# WaterMonitorV6_0.net
KiCad netlist of a schematic drawn in EAGLE
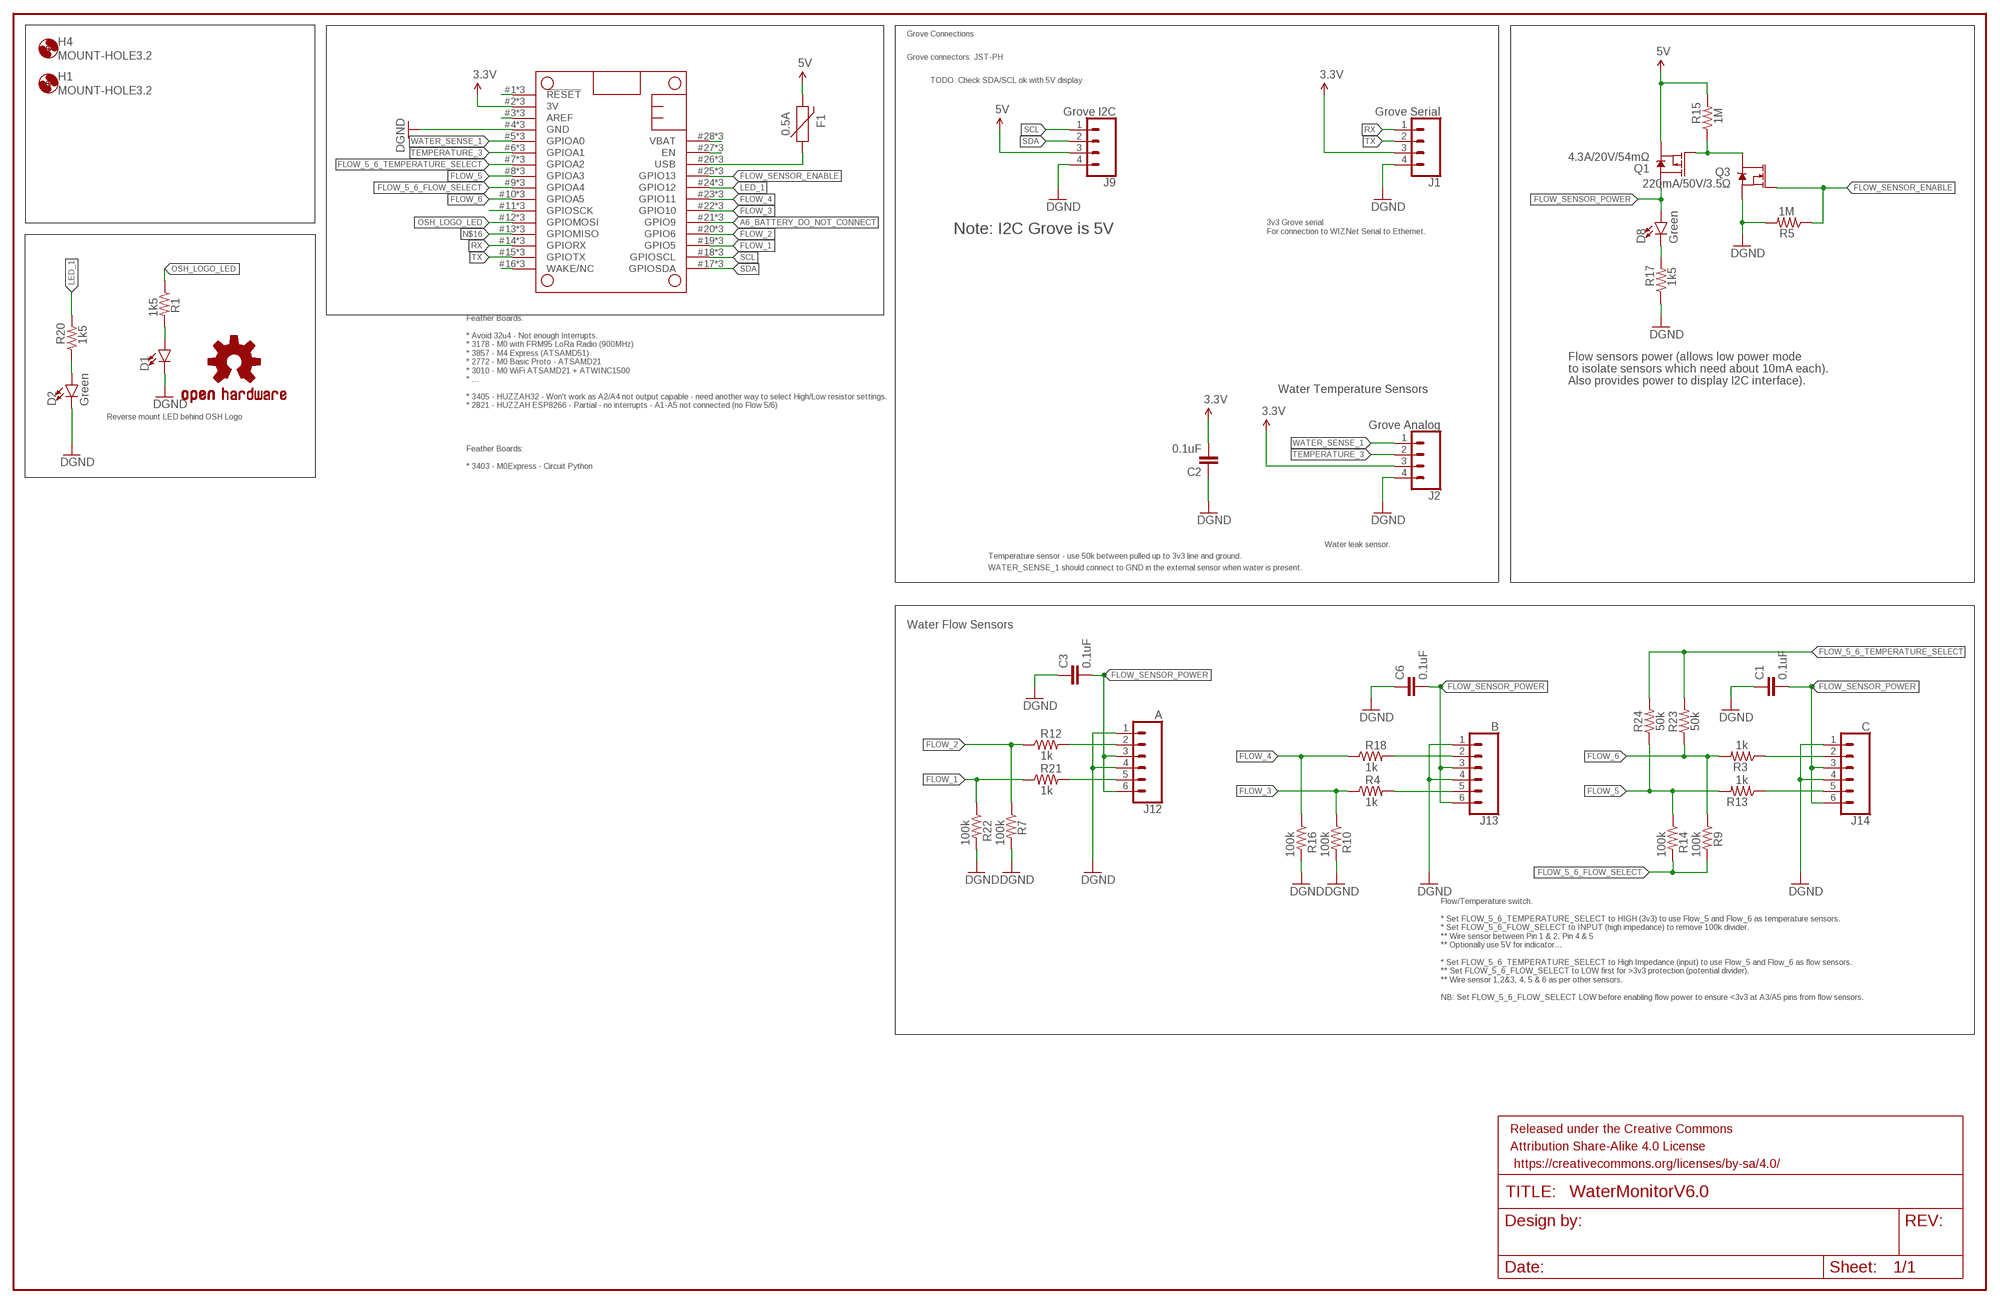
[diagram p0: schematic, sheet 1]

(export (version "E")
  (design (tool "Eeschema 10.0.6"))
  (components
    (comp (ref "C1")
      (value "0.1uF")
      (footprint "eagle-import:0805")
      (libsource (lib "eagle-import") (part "CAP0805"))
    )
    (comp (ref "C2")
      (value "0.1uF")
      (footprint "eagle-import:0805")
      (libsource (lib "eagle-import") (part "CAP0805"))
    )
    (comp (ref "C3")
      (value "0.1uF")
      (footprint "eagle-import:0805")
      (libsource (lib "eagle-import") (part "CAP0805"))
    )
    (comp (ref "C6")
      (value "0.1uF")
      (footprint "eagle-import:0805")
      (libsource (lib "eagle-import") (part "CAP0805"))
    )
    (comp (ref "D1")
      (value "LED1206-BOTTOM")
      (footprint "eagle-import:LED-1206-BOTTOM")
      (libsource (lib "eagle-import") (part "LED1206-BOTTOM"))
    )
    (comp (ref "D2")
      (value "Green")
      (footprint "eagle-import:LED-1206")
      (libsource (lib "eagle-import") (part "LED-BLUE1206"))
    )
    (comp (ref "D8")
      (value "Green")
      (footprint "eagle-import:LED-1206")
      (libsource (lib "eagle-import") (part "LED-BLUE1206"))
    )
    (comp (ref "F1")
      (value "0.5A")
      (footprint "eagle-import:1206")
      (libsource (lib "eagle-import") (part "PPTC_HALF-AMP"))
    )
    (comp (ref "FRAME2")
      (value "FRAME-LEDGER")
      (footprint "eagle-import:CREATIVE_COMMONS")
      (libsource (lib "eagle-import") (part "FRAME-LEDGER"))
    )
    (comp (ref "H1")
      (value "MOUNT-HOLE3.2")
      (footprint "eagle-import:3,2")
      (libsource (lib "eagle-import") (part "MOUNT-HOLE3.2"))
    )
    (comp (ref "H4")
      (value "MOUNT-HOLE3.2")
      (footprint "eagle-import:3,2")
      (libsource (lib "eagle-import") (part "MOUNT-HOLE3.2"))
    )
    (comp (ref "J1")
      (value "Grove Serial")
      (footprint "eagle-import:JST-4-PTH-VERT")
      (libsource (lib "eagle-import") (part "CONN_04JST-PTH-VERT"))
    )
    (comp (ref "J2")
      (value "Grove Analog")
      (footprint "eagle-import:JST-4-PTH-VERT")
      (libsource (lib "eagle-import") (part "CONN_04JST-PTH-VERT"))
    )
    (comp (ref "J9")
      (value "Grove I2C")
      (footprint "eagle-import:JST-4-PTH-VERT")
      (libsource (lib "eagle-import") (part "CONN_04JST-PTH-VERT"))
    )
    (comp (ref "J12")
      (value "A")
      (footprint "eagle-import:RJ11-6")
      (libsource (lib "eagle-import") (part "RJ11-6"))
    )
    (comp (ref "J13")
      (value "B")
      (footprint "eagle-import:RJ11-6")
      (libsource (lib "eagle-import") (part "RJ11-6"))
    )
    (comp (ref "J14")
      (value "C")
      (footprint "eagle-import:RJ11-6")
      (libsource (lib "eagle-import") (part "RJ11-6"))
    )
    (comp (ref "LOGO1")
      (value "OSHW-LOGOM")
      (footprint "eagle-import:OSHW-LOGO-M")
      (libsource (lib "eagle-import") (part "OSHW-LOGOM"))
    )
    (comp (ref "MS1")
      (value "FEATHERWINGFEATHEWING_BREAKOUT")
      (footprint "eagle-import:FEATHERWING_BREAKOUT")
      (libsource (lib "eagle-import") (part "FEATHERWINGFEATHEWING_BREAKOUT"))
    )
    (comp (ref "Q1")
      (value "4.3A/20V/54mΩ")
      (footprint "eagle-import:SOT23-3")
      (libsource (lib "eagle-import") (part "MOSFET_PCH-IRLML2244"))
    )
    (comp (ref "Q3")
      (value "220mA/50V/3.5Ω")
      (footprint "eagle-import:SOT23-3")
      (libsource (lib "eagle-import") (part "MOSFET-NCH-BSS138"))
    )
    (comp (ref "R1")
      (value "1k5")
      (footprint "eagle-import:0805")
      (libsource (lib "eagle-import") (part "RESISTOR0805"))
    )
    (comp (ref "R3")
      (value "1k")
      (footprint "eagle-import:0805")
      (libsource (lib "eagle-import") (part "RESISTOR0805"))
    )
    (comp (ref "R4")
      (value "1k")
      (footprint "eagle-import:0805")
      (libsource (lib "eagle-import") (part "RESISTOR0805"))
    )
    (comp (ref "R5")
      (value "1M")
      (footprint "eagle-import:0805")
      (libsource (lib "eagle-import") (part "RESISTOR0805"))
    )
    (comp (ref "R7")
      (value "100k")
      (footprint "eagle-import:0805")
      (libsource (lib "eagle-import") (part "RESISTOR0805"))
    )
    (comp (ref "R9")
      (value "100k")
      (footprint "eagle-import:0805")
      (libsource (lib "eagle-import") (part "RESISTOR0805"))
    )
    (comp (ref "R10")
      (value "100k")
      (footprint "eagle-import:0805")
      (libsource (lib "eagle-import") (part "RESISTOR0805"))
    )
    (comp (ref "R12")
      (value "1k")
      (footprint "eagle-import:0805")
      (libsource (lib "eagle-import") (part "RESISTOR0805"))
    )
    (comp (ref "R13")
      (value "1k")
      (footprint "eagle-import:0805")
      (libsource (lib "eagle-import") (part "RESISTOR0805"))
    )
    (comp (ref "R14")
      (value "100k")
      (footprint "eagle-import:0805")
      (libsource (lib "eagle-import") (part "RESISTOR0805"))
    )
    (comp (ref "R15")
      (value "1M")
      (footprint "eagle-import:0805")
      (libsource (lib "eagle-import") (part "RESISTOR0805"))
    )
    (comp (ref "R16")
      (value "100k")
      (footprint "eagle-import:0805")
      (libsource (lib "eagle-import") (part "RESISTOR0805"))
    )
    (comp (ref "R17")
      (value "1k5")
      (footprint "eagle-import:0805")
      (libsource (lib "eagle-import") (part "RESISTOR0805"))
    )
    (comp (ref "R18")
      (value "1k")
      (footprint "eagle-import:0805")
      (libsource (lib "eagle-import") (part "RESISTOR0805"))
    )
    (comp (ref "R20")
      (value "1k5")
      (footprint "eagle-import:0805")
      (libsource (lib "eagle-import") (part "RESISTOR0805"))
    )
    (comp (ref "R21")
      (value "1k")
      (footprint "eagle-import:0805")
      (libsource (lib "eagle-import") (part "RESISTOR0805"))
    )
    (comp (ref "R22")
      (value "100k")
      (footprint "eagle-import:0805")
      (libsource (lib "eagle-import") (part "RESISTOR0805"))
    )
    (comp (ref "R23")
      (value "50k")
      (footprint "eagle-import:0805")
      (libsource (lib "eagle-import") (part "RESISTOR0805"))
    )
    (comp (ref "R24")
      (value "50k")
      (footprint "eagle-import:0805")
      (libsource (lib "eagle-import") (part "RESISTOR0805"))
    )
  )
  (nets
    (net (code "1") (name "3.3V") (class "Default")
      (node (ref "C2") (pin "2") (pinfunction "2_2") (pintype "passive"))
      (node (ref "J1") (pin "3") (pinfunction "3_3") (pintype "passive"))
      (node (ref "J2") (pin "3") (pinfunction "3_3") (pintype "passive"))
      (node (ref "MS1") (pin "#2") (pinfunction "3V_#2") (pintype "power_in"))
      (node (ref "MS1") (pin "2") (pinfunction "3V_2") (pintype "power_in"))
      (node (ref "MS1") (pin "@2") (pinfunction "3V_@2") (pintype "power_in"))
    )
    (net (code "2") (name "5V") (class "Default")
      (node (ref "F1") (pin "2") (pinfunction "2_2") (pintype "bidirectional"))
      (node (ref "J9") (pin "3") (pinfunction "3_3") (pintype "passive"))
      (node (ref "Q1") (pin "2") (pinfunction "S_2") (pintype "bidirectional"))
      (node (ref "R15") (pin "2") (pinfunction "2_2") (pintype "passive"))
    )
    (net (code "3") (name "A6_BATTERY_DO_NOT_CONNECT") (class "Default")
      (node (ref "MS1") (pin "#21") (pinfunction "GPIO9_#21") (pintype "bidirectional"))
      (node (ref "MS1") (pin "21") (pinfunction "GPIO9_21") (pintype "bidirectional"))
      (node (ref "MS1") (pin "@21") (pinfunction "GPIO9_@21") (pintype "bidirectional"))
    )
    (net (code "4") (name "DGND") (class "Default")
      (node (ref "C1") (pin "1") (pinfunction "1_1") (pintype "passive"))
      (node (ref "C2") (pin "1") (pinfunction "1_1") (pintype "passive"))
      (node (ref "C3") (pin "1") (pinfunction "1_1") (pintype "passive"))
      (node (ref "C6") (pin "1") (pinfunction "1_1") (pintype "passive"))
      (node (ref "D1") (pin "C") (pinfunction "C_C") (pintype "passive"))
      (node (ref "D2") (pin "C") (pinfunction "C_C") (pintype "passive"))
      (node (ref "J1") (pin "4") (pinfunction "4_4") (pintype "passive"))
      (node (ref "J12") (pin "1") (pinfunction "1_1") (pintype "passive"))
      (node (ref "J12") (pin "4") (pinfunction "4_4") (pintype "passive"))
      (node (ref "J13") (pin "1") (pinfunction "1_1") (pintype "passive"))
      (node (ref "J13") (pin "4") (pinfunction "4_4") (pintype "passive"))
      (node (ref "J14") (pin "1") (pinfunction "1_1") (pintype "passive"))
      (node (ref "J14") (pin "4") (pinfunction "4_4") (pintype "passive"))
      (node (ref "J2") (pin "4") (pinfunction "4_4") (pintype "passive"))
      (node (ref "J9") (pin "4") (pinfunction "4_4") (pintype "passive"))
      (node (ref "MS1") (pin "#4") (pinfunction "GND_#4") (pintype "power_in"))
      (node (ref "MS1") (pin "4") (pinfunction "GND_4") (pintype "power_in"))
      (node (ref "MS1") (pin "@4") (pinfunction "GND_@4") (pintype "power_in"))
      (node (ref "Q3") (pin "2") (pinfunction "S_2") (pintype "bidirectional"))
      (node (ref "R10") (pin "2") (pinfunction "2_2") (pintype "passive"))
      (node (ref "R16") (pin "2") (pinfunction "2_2") (pintype "passive"))
      (node (ref "R17") (pin "1") (pinfunction "1_1") (pintype "passive"))
      (node (ref "R22") (pin "2") (pinfunction "2_2") (pintype "passive"))
      (node (ref "R5") (pin "2") (pinfunction "2_2") (pintype "passive"))
      (node (ref "R7") (pin "2") (pinfunction "2_2") (pintype "passive"))
    )
    (net (code "5") (name "FLOW_1") (class "Default")
      (node (ref "MS1") (pin "#19") (pinfunction "GPIO5_#19") (pintype "bidirectional"))
      (node (ref "MS1") (pin "19") (pinfunction "GPIO5_19") (pintype "bidirectional"))
      (node (ref "MS1") (pin "@19") (pinfunction "GPIO5_@19") (pintype "bidirectional"))
      (node (ref "R21") (pin "1") (pinfunction "1_1") (pintype "passive"))
      (node (ref "R22") (pin "1") (pinfunction "1_1") (pintype "passive"))
    )
    (net (code "6") (name "FLOW_2") (class "Default")
      (node (ref "MS1") (pin "#20") (pinfunction "GPIO6_#20") (pintype "bidirectional"))
      (node (ref "MS1") (pin "20") (pinfunction "GPIO6_20") (pintype "bidirectional"))
      (node (ref "MS1") (pin "@20") (pinfunction "GPIO6_@20") (pintype "bidirectional"))
      (node (ref "R12") (pin "1") (pinfunction "1_1") (pintype "passive"))
      (node (ref "R7") (pin "1") (pinfunction "1_1") (pintype "passive"))
    )
    (net (code "7") (name "FLOW_3") (class "Default")
      (node (ref "MS1") (pin "#22") (pinfunction "GPIO10_#22") (pintype "bidirectional"))
      (node (ref "MS1") (pin "22") (pinfunction "GPIO10_22") (pintype "bidirectional"))
      (node (ref "MS1") (pin "@22") (pinfunction "GPIO10_@22") (pintype "bidirectional"))
      (node (ref "R10") (pin "1") (pinfunction "1_1") (pintype "passive"))
      (node (ref "R4") (pin "1") (pinfunction "1_1") (pintype "passive"))
    )
    (net (code "8") (name "FLOW_4") (class "Default")
      (node (ref "MS1") (pin "#23") (pinfunction "GPIO11_#23") (pintype "bidirectional"))
      (node (ref "MS1") (pin "23") (pinfunction "GPIO11_23") (pintype "bidirectional"))
      (node (ref "MS1") (pin "@23") (pinfunction "GPIO11_@23") (pintype "bidirectional"))
      (node (ref "R16") (pin "1") (pinfunction "1_1") (pintype "passive"))
      (node (ref "R18") (pin "1") (pinfunction "1_1") (pintype "passive"))
    )
    (net (code "9") (name "FLOW_5") (class "Default")
      (node (ref "MS1") (pin "#8") (pinfunction "GPIOA3_#8") (pintype "bidirectional"))
      (node (ref "MS1") (pin "8") (pinfunction "GPIOA3_8") (pintype "bidirectional"))
      (node (ref "MS1") (pin "@8") (pinfunction "GPIOA3_@8") (pintype "bidirectional"))
      (node (ref "R13") (pin "2") (pinfunction "2_2") (pintype "passive"))
      (node (ref "R14") (pin "1") (pinfunction "1_1") (pintype "passive"))
      (node (ref "R24") (pin "1") (pinfunction "1_1") (pintype "passive"))
    )
    (net (code "10") (name "FLOW_5_6_FLOW_SELECT") (class "Default")
      (node (ref "MS1") (pin "#9") (pinfunction "GPIOA4_#9") (pintype "bidirectional"))
      (node (ref "MS1") (pin "9") (pinfunction "GPIOA4_9") (pintype "bidirectional"))
      (node (ref "MS1") (pin "@9") (pinfunction "GPIOA4_@9") (pintype "bidirectional"))
      (node (ref "R14") (pin "2") (pinfunction "2_2") (pintype "passive"))
      (node (ref "R9") (pin "2") (pinfunction "2_2") (pintype "passive"))
    )
    (net (code "11") (name "FLOW_5_6_TEMPERATURE_SELECT") (class "Default")
      (node (ref "MS1") (pin "#7") (pinfunction "GPIOA2_#7") (pintype "bidirectional"))
      (node (ref "MS1") (pin "7") (pinfunction "GPIOA2_7") (pintype "bidirectional"))
      (node (ref "MS1") (pin "@7") (pinfunction "GPIOA2_@7") (pintype "bidirectional"))
      (node (ref "R23") (pin "2") (pinfunction "2_2") (pintype "passive"))
      (node (ref "R24") (pin "2") (pinfunction "2_2") (pintype "passive"))
    )
    (net (code "12") (name "FLOW_6") (class "Default")
      (node (ref "MS1") (pin "#10") (pinfunction "GPIOA5_#10") (pintype "bidirectional"))
      (node (ref "MS1") (pin "10") (pinfunction "GPIOA5_10") (pintype "bidirectional"))
      (node (ref "MS1") (pin "@10") (pinfunction "GPIOA5_@10") (pintype "bidirectional"))
      (node (ref "R23") (pin "1") (pinfunction "1_1") (pintype "passive"))
      (node (ref "R3") (pin "2") (pinfunction "2_2") (pintype "passive"))
      (node (ref "R9") (pin "1") (pinfunction "1_1") (pintype "passive"))
    )
    (net (code "13") (name "FLOW_SENSOR_ENABLE") (class "Default")
      (node (ref "MS1") (pin "#25") (pinfunction "GPIO13_#25") (pintype "bidirectional"))
      (node (ref "MS1") (pin "25") (pinfunction "GPIO13_25") (pintype "bidirectional"))
      (node (ref "MS1") (pin "@25") (pinfunction "GPIO13_@25") (pintype "bidirectional"))
      (node (ref "Q3") (pin "1") (pinfunction "G_1") (pintype "bidirectional"))
      (node (ref "R5") (pin "1") (pinfunction "1_1") (pintype "passive"))
    )
    (net (code "14") (name "FLOW_SENSOR_POWER") (class "Default")
      (node (ref "C1") (pin "2") (pinfunction "2_2") (pintype "passive"))
      (node (ref "C3") (pin "2") (pinfunction "2_2") (pintype "passive"))
      (node (ref "C6") (pin "2") (pinfunction "2_2") (pintype "passive"))
      (node (ref "D8") (pin "A") (pinfunction "A_A") (pintype "passive"))
      (node (ref "J12") (pin "3") (pinfunction "3_3") (pintype "passive"))
      (node (ref "J12") (pin "6") (pinfunction "6_6") (pintype "passive"))
      (node (ref "J13") (pin "3") (pinfunction "3_3") (pintype "passive"))
      (node (ref "J13") (pin "6") (pinfunction "6_6") (pintype "passive"))
      (node (ref "J14") (pin "3") (pinfunction "3_3") (pintype "passive"))
      (node (ref "J14") (pin "6") (pinfunction "6_6") (pintype "passive"))
      (node (ref "Q1") (pin "3") (pinfunction "D_3") (pintype "bidirectional"))
    )
    (net (code "15") (name "LED_1") (class "Default")
      (node (ref "MS1") (pin "#24") (pinfunction "GPIO12_#24") (pintype "bidirectional"))
      (node (ref "MS1") (pin "24") (pinfunction "GPIO12_24") (pintype "bidirectional"))
      (node (ref "MS1") (pin "@24") (pinfunction "GPIO12_@24") (pintype "bidirectional"))
      (node (ref "R20") (pin "2") (pinfunction "2_2") (pintype "passive"))
    )
    (net (code "16") (name "N$16") (class "Default")
      (node (ref "MS1") (pin "#13") (pinfunction "GPIOMISO_#13") (pintype "bidirectional"))
      (node (ref "MS1") (pin "13") (pinfunction "GPIOMISO_13") (pintype "bidirectional"))
      (node (ref "MS1") (pin "@13") (pinfunction "GPIOMISO_@13") (pintype "bidirectional"))
    )
    (net (code "17") (name "Net-(D1-PadA)") (class "Default")
      (node (ref "D1") (pin "A") (pinfunction "A_A") (pintype "passive"))
      (node (ref "R1") (pin "2") (pinfunction "2_2") (pintype "passive"))
    )
    (net (code "18") (name "Net-(D2-PadA)") (class "Default")
      (node (ref "D2") (pin "A") (pinfunction "A_A") (pintype "passive"))
      (node (ref "R20") (pin "1") (pinfunction "1_1") (pintype "passive"))
    )
    (net (code "19") (name "Net-(D8-PadC)") (class "Default")
      (node (ref "D8") (pin "C") (pinfunction "C_C") (pintype "passive"))
      (node (ref "R17") (pin "2") (pinfunction "2_2") (pintype "passive"))
    )
    (net (code "20") (name "Net-(F1-Pad1)") (class "Default")
      (node (ref "F1") (pin "1") (pinfunction "1_1") (pintype "bidirectional"))
      (node (ref "MS1") (pin "#26") (pinfunction "USB_#26") (pintype "power_in"))
      (node (ref "MS1") (pin "26") (pinfunction "USB_26") (pintype "power_in"))
      (node (ref "MS1") (pin "@26") (pinfunction "USB_@26") (pintype "power_in"))
    )
    (net (code "21") (name "Net-(J12-Pad2)") (class "Default")
      (node (ref "J12") (pin "2") (pinfunction "2_2") (pintype "passive"))
      (node (ref "R12") (pin "2") (pinfunction "2_2") (pintype "passive"))
    )
    (net (code "22") (name "Net-(J12-Pad5)") (class "Default")
      (node (ref "J12") (pin "5") (pinfunction "5_5") (pintype "passive"))
      (node (ref "R21") (pin "2") (pinfunction "2_2") (pintype "passive"))
    )
    (net (code "23") (name "Net-(J13-Pad2)") (class "Default")
      (node (ref "J13") (pin "2") (pinfunction "2_2") (pintype "passive"))
      (node (ref "R18") (pin "2") (pinfunction "2_2") (pintype "passive"))
    )
    (net (code "24") (name "Net-(J13-Pad5)") (class "Default")
      (node (ref "J13") (pin "5") (pinfunction "5_5") (pintype "passive"))
      (node (ref "R4") (pin "2") (pinfunction "2_2") (pintype "passive"))
    )
    (net (code "25") (name "Net-(J14-Pad2)") (class "Default")
      (node (ref "J14") (pin "2") (pinfunction "2_2") (pintype "passive"))
      (node (ref "R3") (pin "1") (pinfunction "1_1") (pintype "passive"))
    )
    (net (code "26") (name "Net-(J14-Pad5)") (class "Default")
      (node (ref "J14") (pin "5") (pinfunction "5_5") (pintype "passive"))
      (node (ref "R13") (pin "1") (pinfunction "1_1") (pintype "passive"))
    )
    (net (code "27") (name "Net-(MS1-AREF-Pad#3)") (class "Default")
      (node (ref "MS1") (pin "#3") (pinfunction "AREF_#3") (pintype "passive"))
      (node (ref "MS1") (pin "3") (pinfunction "AREF_3") (pintype "passive"))
      (node (ref "MS1") (pin "@3") (pinfunction "AREF_@3") (pintype "passive"))
    )
    (net (code "28") (name "Net-(MS1-EN-Pad#27)") (class "Default")
      (node (ref "MS1") (pin "#27") (pinfunction "EN_#27") (pintype "passive"))
      (node (ref "MS1") (pin "27") (pinfunction "EN_27") (pintype "passive"))
      (node (ref "MS1") (pin "@27") (pinfunction "EN_@27") (pintype "passive"))
    )
    (net (code "29") (name "Net-(MS1-GPIOSCK-Pad#11)") (class "Default")
      (node (ref "MS1") (pin "#11") (pinfunction "GPIOSCK_#11") (pintype "bidirectional"))
      (node (ref "MS1") (pin "11") (pinfunction "GPIOSCK_11") (pintype "bidirectional"))
      (node (ref "MS1") (pin "@11") (pinfunction "GPIOSCK_@11") (pintype "bidirectional"))
    )
    (net (code "30") (name "Net-(MS1-VBAT-Pad#28)") (class "Default")
      (node (ref "MS1") (pin "#28") (pinfunction "VBAT_#28") (pintype "power_in"))
      (node (ref "MS1") (pin "28") (pinfunction "VBAT_28") (pintype "power_in"))
      (node (ref "MS1") (pin "@28") (pinfunction "VBAT_@28") (pintype "power_in"))
    )
    (net (code "31") (name "Net-(MS1-WAKE{slash}NC-Pad#16)") (class "Default")
      (node (ref "MS1") (pin "#16") (pinfunction "WAKE/NC_#16") (pintype "passive"))
      (node (ref "MS1") (pin "16") (pinfunction "WAKE/NC_16") (pintype "passive"))
      (node (ref "MS1") (pin "@16") (pinfunction "WAKE/NC_@16") (pintype "passive"))
    )
    (net (code "32") (name "Net-(MS1-~{RESET}-Pad#1)") (class "Default")
      (node (ref "MS1") (pin "#1") (pinfunction "~{RESET}_#1") (pintype "input"))
      (node (ref "MS1") (pin "1") (pinfunction "~{RESET}_1") (pintype "input"))
      (node (ref "MS1") (pin "@1") (pinfunction "~{RESET}_@1") (pintype "input"))
    )
    (net (code "33") (name "Net-(Q1-G)") (class "Default")
      (node (ref "Q1") (pin "1") (pinfunction "G_1") (pintype "bidirectional"))
      (node (ref "Q3") (pin "3") (pinfunction "D_3") (pintype "bidirectional"))
      (node (ref "R15") (pin "1") (pinfunction "1_1") (pintype "passive"))
    )
    (net (code "34") (name "OSH_LOGO_LED") (class "Default")
      (node (ref "MS1") (pin "#12") (pinfunction "GPIOMOSI_#12") (pintype "bidirectional"))
      (node (ref "MS1") (pin "12") (pinfunction "GPIOMOSI_12") (pintype "bidirectional"))
      (node (ref "MS1") (pin "@12") (pinfunction "GPIOMOSI_@12") (pintype "bidirectional"))
      (node (ref "R1") (pin "1") (pinfunction "1_1") (pintype "passive"))
    )
    (net (code "35") (name "RX") (class "Default")
      (node (ref "J1") (pin "1") (pinfunction "1_1") (pintype "passive"))
      (node (ref "MS1") (pin "#14") (pinfunction "GPIORX_#14") (pintype "bidirectional"))
      (node (ref "MS1") (pin "14") (pinfunction "GPIORX_14") (pintype "bidirectional"))
      (node (ref "MS1") (pin "@14") (pinfunction "GPIORX_@14") (pintype "bidirectional"))
    )
    (net (code "36") (name "SCL") (class "Default")
      (node (ref "J9") (pin "1") (pinfunction "1_1") (pintype "passive"))
      (node (ref "MS1") (pin "#18") (pinfunction "GPIOSCL_#18") (pintype "bidirectional"))
      (node (ref "MS1") (pin "18") (pinfunction "GPIOSCL_18") (pintype "bidirectional"))
      (node (ref "MS1") (pin "@!8") (pinfunction "GPIOSCL_@!8") (pintype "bidirectional"))
    )
    (net (code "37") (name "SDA") (class "Default")
      (node (ref "J9") (pin "2") (pinfunction "2_2") (pintype "passive"))
      (node (ref "MS1") (pin "#17") (pinfunction "GPIOSDA_#17") (pintype "bidirectional"))
      (node (ref "MS1") (pin "17") (pinfunction "GPIOSDA_17") (pintype "bidirectional"))
      (node (ref "MS1") (pin "@17") (pinfunction "GPIOSDA_@17") (pintype "bidirectional"))
    )
    (net (code "38") (name "TEMPERATURE_3") (class "Default")
      (node (ref "J2") (pin "2") (pinfunction "2_2") (pintype "passive"))
      (node (ref "MS1") (pin "#6") (pinfunction "GPIOA1_#6") (pintype "bidirectional"))
      (node (ref "MS1") (pin "6") (pinfunction "GPIOA1_6") (pintype "bidirectional"))
      (node (ref "MS1") (pin "@6") (pinfunction "GPIOA1_@6") (pintype "bidirectional"))
    )
    (net (code "39") (name "TX") (class "Default")
      (node (ref "J1") (pin "2") (pinfunction "2_2") (pintype "passive"))
      (node (ref "MS1") (pin "#15") (pinfunction "GPIOTX_#15") (pintype "bidirectional"))
      (node (ref "MS1") (pin "15") (pinfunction "GPIOTX_15") (pintype "bidirectional"))
      (node (ref "MS1") (pin "@15") (pinfunction "GPIOTX_@15") (pintype "bidirectional"))
    )
    (net (code "40") (name "WATER_SENSE_1") (class "Default")
      (node (ref "J2") (pin "1") (pinfunction "1_1") (pintype "passive"))
      (node (ref "MS1") (pin "#5") (pinfunction "GPIOA0_#5") (pintype "bidirectional"))
      (node (ref "MS1") (pin "5") (pinfunction "GPIOA0_5") (pintype "bidirectional"))
      (node (ref "MS1") (pin "@5") (pinfunction "GPIOA0_@5") (pintype "bidirectional"))
    )
  )
)
